# Sheet1.net
KiCad netlist of a schematic drawn in Altium Designer
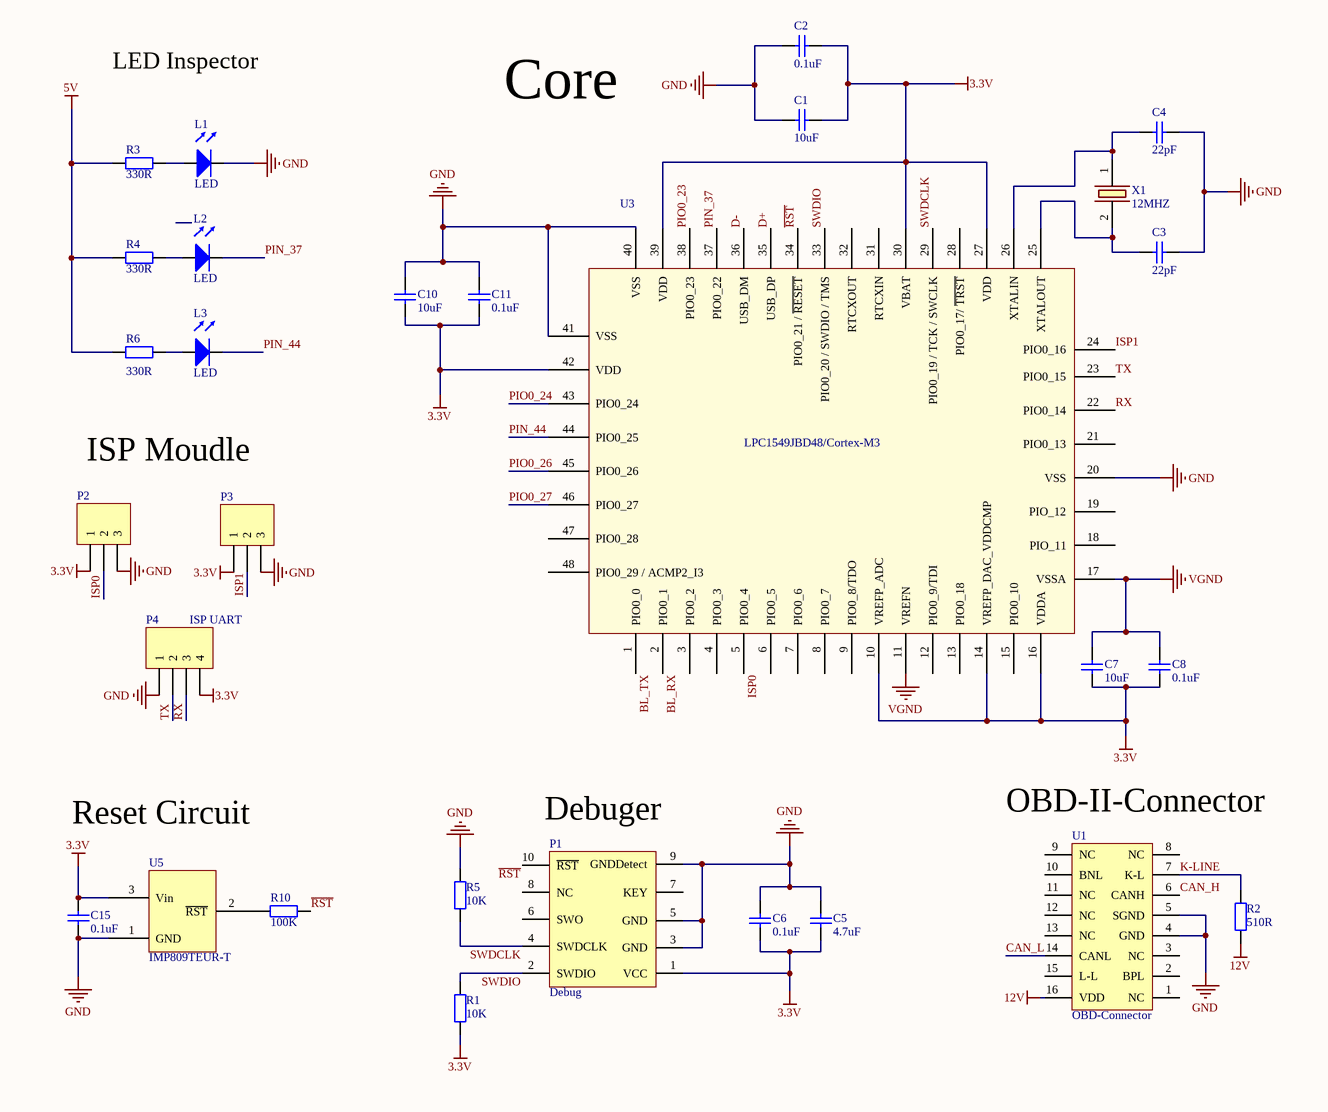
[diagram p0: Sheet1.SchDoc]

(export (version "E")
  (design (tool "Eeschema 10.0.6"))
  (components
    (comp (ref "C1")
      (value "10uF")
      (footprint "0603")
      (description "ceramic")
      (libsource (lib "ToponLib") (part "Cap1"))
    )
    (comp (ref "C2")
      (value "0.1uF")
      (footprint "0603")
      (description "ceramic")
      (libsource (lib "ToponLib") (part "Cap1"))
    )
    (comp (ref "C3")
      (value "22pF")
      (footprint "0603")
      (description "ceramic")
      (libsource (lib "ToponLib") (part "Cap1"))
    )
    (comp (ref "C4")
      (value "22pF")
      (footprint "0603")
      (description "ceramic")
      (libsource (lib "ToponLib") (part "Cap1"))
    )
    (comp (ref "C5")
      (value "4.7uF")
      (footprint "0603")
      (description "ceramic")
      (libsource (lib "ToponLib") (part "Cap1"))
    )
    (comp (ref "C6")
      (value "0.1uF")
      (footprint "0603")
      (description "ceramic")
      (libsource (lib "ToponLib") (part "Cap1"))
    )
    (comp (ref "C7")
      (value "10uF")
      (footprint "0603")
      (description "ceramic")
      (libsource (lib "ToponLib") (part "Cap1"))
    )
    (comp (ref "C8")
      (value "0.1uF")
      (footprint "0603")
      (description "ceramic")
      (libsource (lib "ToponLib") (part "Cap1"))
    )
    (comp (ref "C10")
      (value "10uF")
      (footprint "0603")
      (description "ceramic")
      (libsource (lib "ToponLib") (part "Cap1"))
    )
    (comp (ref "C11")
      (value "0.1uF")
      (footprint "0603")
      (description "ceramic")
      (libsource (lib "ToponLib") (part "Cap1"))
    )
    (comp (ref "C15")
      (value "0.1uF")
      (footprint "0603")
      (description "ceramic")
      (libsource (lib "ToponLib") (part "Cap1"))
    )
    (comp (ref "L1") (value "LED") (footprint "0805") (libsource (lib "ToponLib") (part "LED")))
    (comp (ref "L2") (value "LED") (footprint "0805") (libsource (lib "ToponLib") (part "LED")))
    (comp (ref "L3") (value "LED") (footprint "0805") (libsource (lib "ToponLib") (part "LED")))
    (comp (ref "P1")
      (value "Debug")
      (footprint "JATG_10pin")
      (libsource (lib "ToponLib") (part "JTAG_10Pin"))
    )
    (comp (ref "P2")
      (value "~")
      (footprint "HDR1X3")
      (description "Header, 3-Pin")
      (fields (field (name "PUBLISHER") "Altium Limited"))
      (libsource (lib "Miscellaneous Connectors") (part "Header 3"))
    )
    (comp (ref "P3")
      (value "~")
      (footprint "HDR1X3")
      (description "Header, 3-Pin")
      (fields (field (name "PUBLISHER") "Altium Limited"))
      (libsource (lib "Miscellaneous Connectors") (part "Header 3"))
    )
    (comp (ref "P4")
      (value "ISP UART")
      (footprint "HDR1X4")
      (description "Header, 4-Pin")
      (fields (field (name "PUBLISHER") "Altium Limited"))
      (libsource (lib "Miscellaneous Connectors") (part "Header 4"))
    )
    (comp (ref "R1") (value "10K") (footprint "0603") (libsource (lib "ToponLib") (part "Res")))
    (comp (ref "R2") (value "510R") (footprint "0603") (libsource (lib "ToponLib") (part "Res")))
    (comp (ref "R3") (value "330R") (footprint "0603") (libsource (lib "") (part "Res_1")))
    (comp (ref "R4") (value "330R") (footprint "0603") (libsource (lib "") (part "Res_1")))
    (comp (ref "R5") (value "10K") (footprint "0603") (libsource (lib "ToponLib") (part "Res")))
    (comp (ref "R6") (value "330R") (footprint "0603") (libsource (lib "") (part "Res_1")))
    (comp (ref "R10") (value "100K") (footprint "0603") (libsource (lib "") (part "Res_2")))
    (comp (ref "U1")
      (value "OBD-Connector")
      (footprint "OBD-MaleConnector")
      (libsource (lib "ToponLib") (part "OBD-MaleHead"))
    )
    (comp (ref "U3")
      (value "LPC1549")
      (footprint "LPC1549JBD48")
      (libsource (lib "ToponLib") (part "LPC1549JBD48"))
    )
    (comp (ref "U5")
      (value "IMP809TEUR-T")
      (footprint "SOT23-3")
      (libsource (lib "ToponLib") (part "IMP809TEUR-T"))
    )
    (comp (ref "X1") (value "12MHZ") (footprint "12Mhz-DFN") (libsource (lib "ToponLib") (part "OSC")))
  )
  (nets
    (net (code "1") (name "/BL_RX") (class "Default")
      (node (ref "U3") (pin "2") (pinfunction "PIO0_1_2") (pintype "passive"))
    )
    (net (code "2") (name "/BL_TX") (class "Default")
      (node (ref "U3") (pin "1") (pinfunction "PIO0_0_1") (pintype "passive"))
    )
    (net (code "3") (name "/CAN_H") (class "Default")
      (node (ref "U1") (pin "6") (pinfunction "CANH_6") (pintype "passive"))
    )
    (net (code "4") (name "/CAN_L") (class "Default")
      (node (ref "U1") (pin "14") (pinfunction "CANL_14") (pintype "passive"))
    )
    (net (code "5") (name "/D+") (class "Default")
      (node (ref "U3") (pin "35") (pinfunction "USB_DP_35") (pintype "passive"))
    )
    (net (code "6") (name "/D-") (class "Default")
      (node (ref "U3") (pin "36") (pinfunction "USB_DM_36") (pintype "passive"))
    )
    (net (code "7") (name "/ISP0") (class "Default")
      (node (ref "P2") (pin "2") (pinfunction "2_2") (pintype "passive"))
      (node (ref "U3") (pin "5") (pinfunction "PIO0_4_5") (pintype "passive"))
    )
    (net (code "8") (name "/ISP1") (class "Default")
      (node (ref "P3") (pin "2") (pinfunction "2_2") (pintype "passive"))
      (node (ref "U3") (pin "24") (pinfunction "PIO0_16_24") (pintype "passive"))
    )
    (net (code "9") (name "/K-LINE") (class "Default")
      (node (ref "R2") (pin "2") (pinfunction "2_2") (pintype "passive"))
      (node (ref "U1") (pin "7") (pinfunction "K-L_7") (pintype "passive"))
    )
    (net (code "10") (name "/PIN_37") (class "Default")
      (node (ref "L2") (pin "2") (pinfunction "K_2") (pintype "passive"))
      (node (ref "U3") (pin "37") (pinfunction "PIO0_22_37") (pintype "passive"))
    )
    (net (code "11") (name "/PIN_44") (class "Default")
      (node (ref "L3") (pin "2") (pinfunction "K_2") (pintype "passive"))
      (node (ref "U3") (pin "44") (pinfunction "PIO0_25_44") (pintype "passive"))
    )
    (net (code "12") (name "/PIO0_23") (class "Default")
      (node (ref "U3") (pin "38") (pinfunction "PIO0_23_38") (pintype "passive"))
    )
    (net (code "13") (name "/PIO0_24") (class "Default")
      (node (ref "U3") (pin "43") (pinfunction "PIO0_24_43") (pintype "passive"))
    )
    (net (code "14") (name "/PIO0_26") (class "Default")
      (node (ref "U3") (pin "45") (pinfunction "PIO0_26_45") (pintype "passive"))
    )
    (net (code "15") (name "/PIO0_27") (class "Default")
      (node (ref "U3") (pin "46") (pinfunction "PIO0_27_46") (pintype "passive"))
    )
    (net (code "16") (name "/RX") (class "Default")
      (node (ref "P4") (pin "3") (pinfunction "3_3") (pintype "passive"))
      (node (ref "U3") (pin "22") (pinfunction "PIO0_14_22") (pintype "passive"))
    )
    (net (code "17") (name "/SWDCLK") (class "Default")
      (node (ref "P1") (pin "4") (pinfunction "SWDCLK_4") (pintype "passive"))
      (node (ref "R5") (pin "1") (pinfunction "1_1") (pintype "passive"))
      (node (ref "U3") (pin "29") (pinfunction "PIO0_19_/_TCK_/_SWCLK_29") (pintype "passive"))
    )
    (net (code "18") (name "/SWDIO") (class "Default")
      (node (ref "P1") (pin "2") (pinfunction "SWDIO_2") (pintype "passive"))
      (node (ref "R1") (pin "2") (pinfunction "2_2") (pintype "passive"))
      (node (ref "U3") (pin "33") (pinfunction "PIO0_20_/_SWDIO_/_TMS_33") (pintype "passive"))
    )
    (net (code "19") (name "/TX") (class "Default")
      (node (ref "P4") (pin "2") (pinfunction "2_2") (pintype "passive"))
      (node (ref "U3") (pin "23") (pinfunction "PIO0_15_23") (pintype "passive"))
    )
    (net (code "20") (name "/~{RST}") (class "Default")
      (node (ref "P1") (pin "10") (pinfunction "~{RST}_10") (pintype "passive"))
      (node (ref "R10") (pin "1") (pinfunction "1_1") (pintype "passive"))
      (node (ref "U3") (pin "34") (pinfunction "PIO0_21_/_~{RESET}_34") (pintype "passive"))
    )
    (net (code "21") (name "3.3V") (class "Default")
      (node (ref "C1") (pin "2") (pinfunction "2_2") (pintype "passive"))
      (node (ref "C10") (pin "1") (pinfunction "1_1") (pintype "passive"))
      (node (ref "C11") (pin "1") (pinfunction "1_1") (pintype "passive"))
      (node (ref "C15") (pin "2") (pinfunction "2_2") (pintype "passive"))
      (node (ref "C2") (pin "2") (pinfunction "2_2") (pintype "passive"))
      (node (ref "C5") (pin "2") (pinfunction "2_2") (pintype "passive"))
      (node (ref "C6") (pin "2") (pinfunction "2_2") (pintype "passive"))
      (node (ref "C7") (pin "1") (pinfunction "1_1") (pintype "passive"))
      (node (ref "C8") (pin "1") (pinfunction "1_1") (pintype "passive"))
      (node (ref "P1") (pin "1") (pinfunction "VCC_1") (pintype "passive"))
      (node (ref "P2") (pin "1") (pinfunction "1_1") (pintype "passive"))
      (node (ref "P3") (pin "1") (pinfunction "1_1") (pintype "passive"))
      (node (ref "P4") (pin "4") (pinfunction "4_4") (pintype "passive"))
      (node (ref "R1") (pin "1") (pinfunction "1_1") (pintype "passive"))
      (node (ref "U3") (pin "10") (pinfunction "VREFP_ADC_10") (pintype "passive"))
      (node (ref "U3") (pin "14") (pinfunction "VREFP_DAC_VDDCMP_14") (pintype "passive"))
      (node (ref "U3") (pin "16") (pinfunction "VDDA_16") (pintype "passive"))
      (node (ref "U3") (pin "27") (pinfunction "VDD_27") (pintype "passive"))
      (node (ref "U3") (pin "30") (pinfunction "VBAT_30") (pintype "passive"))
      (node (ref "U3") (pin "39") (pinfunction "VDD_39") (pintype "passive"))
      (node (ref "U3") (pin "42") (pinfunction "VDD_42") (pintype "passive"))
      (node (ref "U5") (pin "3") (pinfunction "Vin_3") (pintype "passive"))
    )
    (net (code "22") (name "5V") (class "Default")
      (node (ref "R3") (pin "1") (pinfunction "1_1") (pintype "passive"))
      (node (ref "R4") (pin "1") (pinfunction "1_1") (pintype "passive"))
      (node (ref "R6") (pin "1") (pinfunction "1_1") (pintype "passive"))
    )
    (net (code "23") (name "12V") (class "Default")
      (node (ref "R2") (pin "1") (pinfunction "1_1") (pintype "passive"))
      (node (ref "U1") (pin "16") (pinfunction "VDD_16") (pintype "passive"))
    )
    (net (code "24") (name "GND") (class "Default")
      (node (ref "C1") (pin "1") (pinfunction "1_1") (pintype "passive"))
      (node (ref "C10") (pin "2") (pinfunction "2_2") (pintype "passive"))
      (node (ref "C11") (pin "2") (pinfunction "2_2") (pintype "passive"))
      (node (ref "C15") (pin "1") (pinfunction "1_1") (pintype "passive"))
      (node (ref "C2") (pin "1") (pinfunction "1_1") (pintype "passive"))
      (node (ref "C3") (pin "2") (pinfunction "2_2") (pintype "passive"))
      (node (ref "C4") (pin "2") (pinfunction "2_2") (pintype "passive"))
      (node (ref "C5") (pin "1") (pinfunction "1_1") (pintype "passive"))
      (node (ref "C6") (pin "1") (pinfunction "1_1") (pintype "passive"))
      (node (ref "L1") (pin "2") (pinfunction "K_2") (pintype "passive"))
      (node (ref "P1") (pin "3") (pinfunction "GND_3") (pintype "passive"))
      (node (ref "P1") (pin "5") (pinfunction "GND_5") (pintype "passive"))
      (node (ref "P1") (pin "9") (pinfunction "GNDDetect_9") (pintype "passive"))
      (node (ref "P2") (pin "3") (pinfunction "3_3") (pintype "passive"))
      (node (ref "P3") (pin "3") (pinfunction "3_3") (pintype "passive"))
      (node (ref "P4") (pin "1") (pinfunction "1_1") (pintype "passive"))
      (node (ref "R5") (pin "2") (pinfunction "2_2") (pintype "passive"))
      (node (ref "U1") (pin "4") (pinfunction "GND_4") (pintype "passive"))
      (node (ref "U1") (pin "5") (pinfunction "SGND_5") (pintype "passive"))
      (node (ref "U3") (pin "20") (pinfunction "VSS_20") (pintype "passive"))
      (node (ref "U3") (pin "40") (pinfunction "VSS_40") (pintype "passive"))
      (node (ref "U3") (pin "41") (pinfunction "VSS_41") (pintype "passive"))
      (node (ref "U5") (pin "1") (pinfunction "GND_1") (pintype "passive"))
    )
    (net (code "25") (name "Net-(L1-A)") (class "Default")
      (node (ref "L1") (pin "1") (pinfunction "A_1") (pintype "passive"))
      (node (ref "R3") (pin "2") (pinfunction "2_2") (pintype "passive"))
    )
    (net (code "26") (name "Net-(L2-A)") (class "Default")
      (node (ref "L2") (pin "1") (pinfunction "A_1") (pintype "passive"))
      (node (ref "R4") (pin "2") (pinfunction "2_2") (pintype "passive"))
    )
    (net (code "27") (name "Net-(L3-A)") (class "Default")
      (node (ref "L3") (pin "1") (pinfunction "A_1") (pintype "passive"))
      (node (ref "R6") (pin "2") (pinfunction "2_2") (pintype "passive"))
    )
    (net (code "28") (name "Net-(U3-XTALIN)") (class "Default")
      (node (ref "C4") (pin "1") (pinfunction "1_1") (pintype "passive"))
      (node (ref "U3") (pin "26") (pinfunction "XTALIN_26") (pintype "passive"))
      (node (ref "X1") (pin "1") (pinfunction "1_1") (pintype "passive"))
    )
    (net (code "29") (name "Net-(U3-XTALOUT)") (class "Default")
      (node (ref "C3") (pin "1") (pinfunction "1_1") (pintype "passive"))
      (node (ref "U3") (pin "25") (pinfunction "XTALOUT_25") (pintype "passive"))
      (node (ref "X1") (pin "2") (pinfunction "2_2") (pintype "passive"))
    )
    (net (code "30") (name "Net-(U5-~{RST})") (class "Default")
      (node (ref "R10") (pin "2") (pinfunction "2_2") (pintype "passive"))
      (node (ref "U5") (pin "2") (pinfunction "~{RST}_2") (pintype "passive"))
    )
    (net (code "31") (name "VGND") (class "Default")
      (node (ref "C7") (pin "2") (pinfunction "2_2") (pintype "passive"))
      (node (ref "C8") (pin "2") (pinfunction "2_2") (pintype "passive"))
      (node (ref "U3") (pin "11") (pinfunction "VREFN_11") (pintype "passive"))
      (node (ref "U3") (pin "17") (pinfunction "VSSA_17") (pintype "passive"))
    )
    (net (code "32") (name "unconnected-(P1-KEY-Pad7)") (class "Default")
      (node (ref "P1") (pin "7") (pinfunction "KEY_7") (pintype "passive"))
    )
    (net (code "33") (name "unconnected-(P1-NC-Pad8)") (class "Default")
      (node (ref "P1") (pin "8") (pinfunction "NC_8") (pintype "passive"))
    )
    (net (code "34") (name "unconnected-(P1-SWO-Pad6)") (class "Default")
      (node (ref "P1") (pin "6") (pinfunction "SWO_6") (pintype "passive"))
    )
    (net (code "35") (name "unconnected-(U1-BNL-Pad10)") (class "Default")
      (node (ref "U1") (pin "10") (pinfunction "BNL_10") (pintype "passive"))
    )
    (net (code "36") (name "unconnected-(U1-BPL-Pad2)") (class "Default")
      (node (ref "U1") (pin "2") (pinfunction "BPL_2") (pintype "passive"))
    )
    (net (code "37") (name "unconnected-(U1-L-L-Pad15)") (class "Default")
      (node (ref "U1") (pin "15") (pinfunction "L-L_15") (pintype "passive"))
    )
    (net (code "38") (name "unconnected-(U1-NC-Pad1)") (class "Default")
      (node (ref "U1") (pin "1") (pinfunction "NC_1") (pintype "passive"))
    )
    (net (code "39") (name "unconnected-(U1-NC-Pad3)") (class "Default")
      (node (ref "U1") (pin "3") (pinfunction "NC_3") (pintype "passive"))
    )
    (net (code "40") (name "unconnected-(U1-NC-Pad8)") (class "Default")
      (node (ref "U1") (pin "8") (pinfunction "NC_8") (pintype "passive"))
    )
    (net (code "41") (name "unconnected-(U1-NC-Pad9)") (class "Default")
      (node (ref "U1") (pin "9") (pinfunction "NC_9") (pintype "passive"))
    )
    (net (code "42") (name "unconnected-(U1-NC-Pad11)") (class "Default")
      (node (ref "U1") (pin "11") (pinfunction "NC_11") (pintype "passive"))
    )
    (net (code "43") (name "unconnected-(U1-NC-Pad12)") (class "Default")
      (node (ref "U1") (pin "12") (pinfunction "NC_12") (pintype "passive"))
    )
    (net (code "44") (name "unconnected-(U1-NC-Pad13)") (class "Default")
      (node (ref "U1") (pin "13") (pinfunction "NC_13") (pintype "passive"))
    )
    (net (code "45") (name "unconnected-(U3-PIO0_2-Pad3)") (class "Default")
      (node (ref "U3") (pin "3") (pinfunction "PIO0_2_3") (pintype "passive"))
    )
    (net (code "46") (name "unconnected-(U3-PIO0_3-Pad4)") (class "Default")
      (node (ref "U3") (pin "4") (pinfunction "PIO0_3_4") (pintype "passive"))
    )
    (net (code "47") (name "unconnected-(U3-PIO0_5-Pad6)") (class "Default")
      (node (ref "U3") (pin "6") (pinfunction "PIO0_5_6") (pintype "passive"))
    )
    (net (code "48") (name "unconnected-(U3-PIO0_6-Pad7)") (class "Default")
      (node (ref "U3") (pin "7") (pinfunction "PIO0_6_7") (pintype "passive"))
    )
    (net (code "49") (name "unconnected-(U3-PIO0_7-Pad8)") (class "Default")
      (node (ref "U3") (pin "8") (pinfunction "PIO0_7_8") (pintype "passive"))
    )
    (net (code "50") (name "unconnected-(U3-PIO0_8{slash}TDO-Pad9)") (class "Default")
      (node (ref "U3") (pin "9") (pinfunction "PIO0_8/TDO_9") (pintype "passive"))
    )
    (net (code "51") (name "unconnected-(U3-PIO0_9{slash}TDI-Pad12)") (class "Default")
      (node (ref "U3") (pin "12") (pinfunction "PIO0_9/TDI_12") (pintype "passive"))
    )
    (net (code "52") (name "unconnected-(U3-PIO0_10-Pad15)") (class "Default")
      (node (ref "U3") (pin "15") (pinfunction "PIO0_10_15") (pintype "passive"))
    )
    (net (code "53") (name "unconnected-(U3-PIO0_13-Pad21)") (class "Default")
      (node (ref "U3") (pin "21") (pinfunction "PIO0_13_21") (pintype "passive"))
    )
    (net (code "54") (name "unconnected-(U3-PIO0_17{slash}_~{TRST}-Pad28)") (class "Default")
      (node (ref "U3") (pin "28") (pinfunction "PIO0_17/_~{TRST}_28") (pintype "passive"))
    )
    (net (code "55") (name "unconnected-(U3-PIO0_18-Pad13)") (class "Default")
      (node (ref "U3") (pin "13") (pinfunction "PIO0_18_13") (pintype "passive"))
    )
    (net (code "56") (name "unconnected-(U3-PIO0_28-Pad47)") (class "Default")
      (node (ref "U3") (pin "47") (pinfunction "PIO0_28_47") (pintype "passive"))
    )
    (net (code "57") (name "unconnected-(U3-PIO0_29_{slash}_ACMP2_I3-Pad48)") (class "Default")
      (node (ref "U3") (pin "48") (pinfunction "PIO0_29_/_ACMP2_I3_48") (pintype "passive"))
    )
    (net (code "58") (name "unconnected-(U3-PIO_11-Pad18)") (class "Default")
      (node (ref "U3") (pin "18") (pinfunction "PIO_11_18") (pintype "passive"))
    )
    (net (code "59") (name "unconnected-(U3-PIO_12-Pad19)") (class "Default")
      (node (ref "U3") (pin "19") (pinfunction "PIO_12_19") (pintype "passive"))
    )
    (net (code "60") (name "unconnected-(U3-RTCXIN-Pad31)") (class "Default")
      (node (ref "U3") (pin "31") (pinfunction "RTCXIN_31") (pintype "passive"))
    )
    (net (code "61") (name "unconnected-(U3-RTCXOUT-Pad32)") (class "Default")
      (node (ref "U3") (pin "32") (pinfunction "RTCXOUT_32") (pintype "passive"))
    )
  )
)
